# untitled.net
KiCad netlist of a schematic drawn in EAGLE
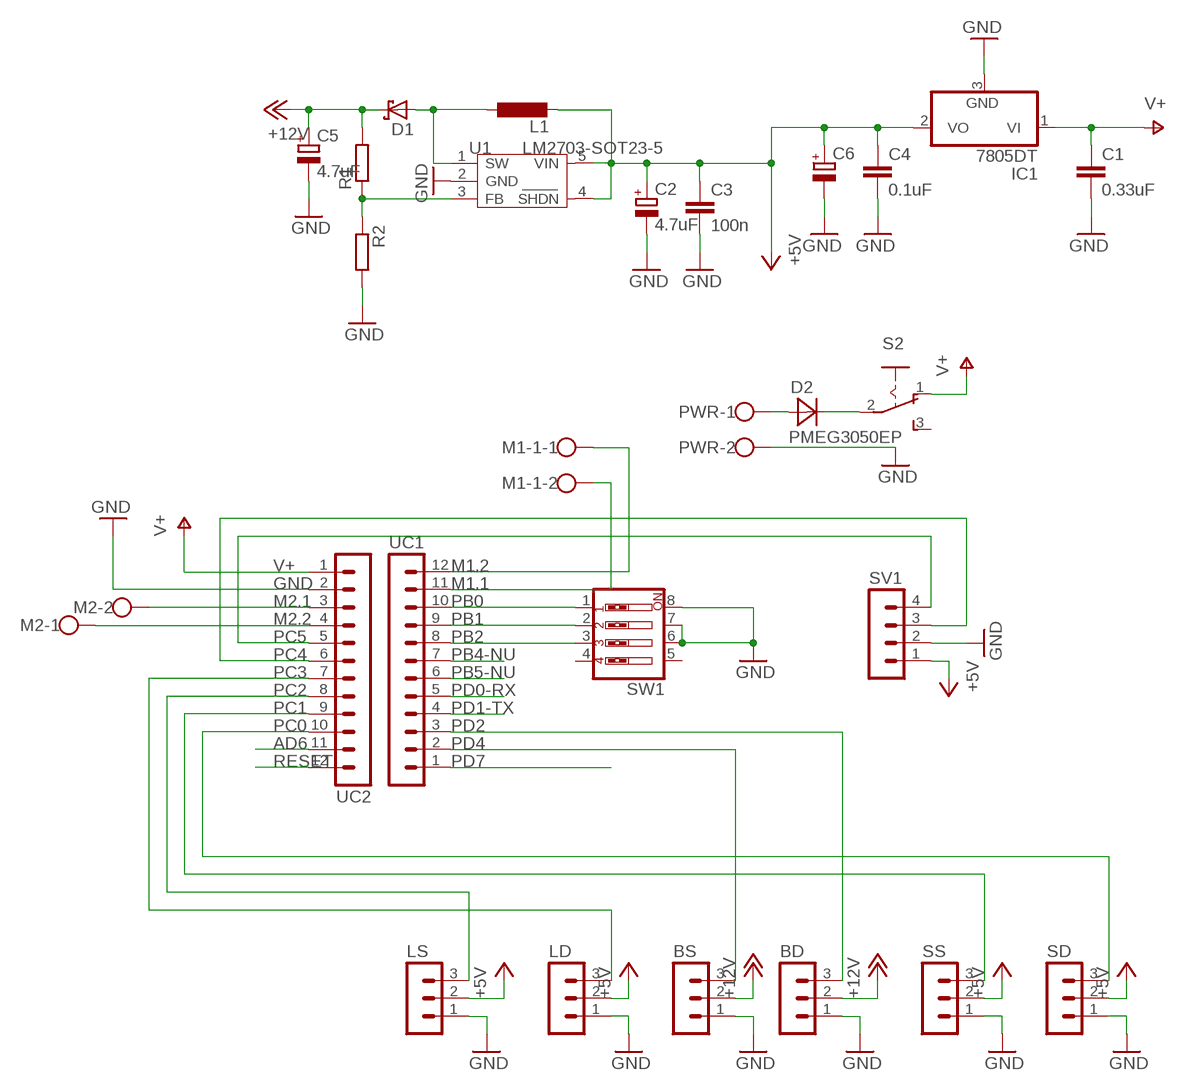
[diagram p0: schematic, sheet 1]

(export (version "E")
  (design (tool "Eeschema 10.0.6"))
  (components
    (comp (ref "BD")
      (value "MA03-1")
      (footprint "eagle-import:MA03-1")
      (libsource (lib "eagle-import") (part "MA03-1"))
    )
    (comp (ref "BS")
      (value "MA03-1")
      (footprint "eagle-import:MA03-1")
      (libsource (lib "eagle-import") (part "MA03-1"))
    )
    (comp (ref "C1")
      (value "0.33uF")
      (footprint "eagle-import:C0805")
      (libsource (lib "eagle-import") (part "C-EUC0805"))
    )
    (comp (ref "C2")
      (value "4.7uF")
      (footprint "eagle-import:153CLV-0405")
      (libsource (lib "eagle-import") (part "CPOL-EU153CLV-0405"))
    )
    (comp (ref "C3")
      (value "100n")
      (footprint "eagle-import:C0805")
      (libsource (lib "eagle-import") (part "C-EUC0805"))
    )
    (comp (ref "C4")
      (value "0.1uF")
      (footprint "eagle-import:C0805")
      (libsource (lib "eagle-import") (part "C-EUC0805"))
    )
    (comp (ref "C5")
      (value "4.7uF")
      (footprint "eagle-import:153CLV-0405")
      (libsource (lib "eagle-import") (part "CPOL-EU153CLV-0405"))
    )
    (comp (ref "C6")
      (value "CPOL-EU153CLV-0605")
      (footprint "eagle-import:153CLV-0605")
      (libsource (lib "eagle-import") (part "CPOL-EU153CLV-0605"))
    )
    (comp (ref "D1")
      (value "SCHOTTKY-DIODESMD")
      (footprint "eagle-import:SMB")
      (libsource (lib "eagle-import") (part "SCHOTTKY-DIODESMD"))
    )
    (comp (ref "D2")
      (value "PMEG3050EP")
      (footprint "eagle-import:SMA")
      (libsource (lib "eagle-import") (part "MBRA340T3"))
    )
    (comp (ref "IC1")
      (value "7805DT")
      (footprint "eagle-import:TO252")
      (libsource (lib "eagle-import") (part "78DT05"))
    )
    (comp (ref "L1")
      (value "L-EUL4532C")
      (footprint "eagle-import:L4532M")
      (libsource (lib "eagle-import") (part "L-EUL4532C"))
    )
    (comp (ref "LD")
      (value "MA03-1")
      (footprint "eagle-import:MA03-1")
      (libsource (lib "eagle-import") (part "MA03-1"))
    )
    (comp (ref "LS")
      (value "MA03-1")
      (footprint "eagle-import:MA03-1")
      (libsource (lib "eagle-import") (part "MA03-1"))
    )
    (comp (ref "M1-1")
      (value "W237-102")
      (footprint "eagle-import:W237-102")
      (fields (field (name "MPN") "237-102"))
      (libsource (lib "eagle-import") (part "W237-102"))
    )
    (comp (ref "M2")
      (value "W237-102")
      (footprint "eagle-import:W237-102")
      (fields (field (name "MPN") "237-102"))
      (libsource (lib "eagle-import") (part "W237-102"))
    )
    (comp (ref "PWR")
      (value "W237-102")
      (footprint "eagle-import:W237-102")
      (fields (field (name "MPN") "237-102"))
      (libsource (lib "eagle-import") (part "W237-102"))
    )
    (comp (ref "R1")
      (value "R-EU_R0805")
      (footprint "eagle-import:R0805")
      (libsource (lib "eagle-import") (part "R-EU_R0805"))
    )
    (comp (ref "R2")
      (value "R-EU_R0805")
      (footprint "eagle-import:R0805")
      (libsource (lib "eagle-import") (part "R-EU_R0805"))
    )
    (comp (ref "S2")
      (value "M251")
      (footprint "eagle-import:M251")
      (libsource (lib "eagle-import") (part "M251"))
    )
    (comp (ref "SD")
      (value "MA03-1")
      (footprint "eagle-import:MA03-1")
      (libsource (lib "eagle-import") (part "MA03-1"))
    )
    (comp (ref "SS")
      (value "MA03-1")
      (footprint "eagle-import:MA03-1")
      (libsource (lib "eagle-import") (part "MA03-1"))
    )
    (comp (ref "SV1")
      (value "MA04-1")
      (footprint "eagle-import:MA04-1")
      (libsource (lib "eagle-import") (part "MA04-1"))
    )
    (comp (ref "SW1")
      (value "SW_DIP-4")
      (footprint "eagle-import:EDG-04")
      (libsource (lib "eagle-import") (part "SW_DIP-4"))
    )
    (comp (ref "U1")
      (value "LM2703-SOT23-5")
      (footprint "eagle-import:SOT23-5")
      (libsource (lib "eagle-import") (part "LM2703-SOT23-5"))
    )
    (comp (ref "UC1")
      (value "MA12-1")
      (footprint "eagle-import:MA12-1")
      (fields (field (name "OC_FARNELL") "unknown") (field (name "OC_NEWARK") "unknown"))
      (libsource (lib "eagle-import") (part "MA12-1"))
    )
    (comp (ref "UC2")
      (value "MA12-1")
      (footprint "eagle-import:MA12-1")
      (libsource (lib "eagle-import") (part "MA12-1"))
    )
  )
  (nets
    (net (code "1") (name "+5V") (class "Default")
      (node (ref "C2") (pin "+") (pinfunction "+_+") (pintype "passive"))
      (node (ref "C3") (pin "1") (pinfunction "1_1") (pintype "passive"))
      (node (ref "C4") (pin "1") (pinfunction "1_1") (pintype "passive"))
      (node (ref "C6") (pin "+") (pinfunction "+_+") (pintype "passive"))
      (node (ref "IC1") (pin "2") (pinfunction "VO_2") (pintype "passive"))
      (node (ref "L1") (pin "2") (pinfunction "2_2") (pintype "passive"))
      (node (ref "LD") (pin "2") (pinfunction "2_2") (pintype "passive"))
      (node (ref "LS") (pin "2") (pinfunction "2_2") (pintype "passive"))
      (node (ref "SD") (pin "2") (pinfunction "2_2") (pintype "passive"))
      (node (ref "SS") (pin "2") (pinfunction "2_2") (pintype "passive"))
      (node (ref "SV1") (pin "1") (pinfunction "1_1") (pintype "passive"))
      (node (ref "U1") (pin "4") (pinfunction "SHDN_4") (pintype "bidirectional"))
      (node (ref "U1") (pin "5") (pinfunction "VIN_5") (pintype "input"))
    )
    (net (code "2") (name "+12V") (class "Default")
      (node (ref "BD") (pin "2") (pinfunction "2_2") (pintype "passive"))
      (node (ref "BS") (pin "2") (pinfunction "2_2") (pintype "passive"))
      (node (ref "C5") (pin "+") (pinfunction "+_+") (pintype "passive"))
      (node (ref "D1") (pin "C") (pinfunction "C_C") (pintype "passive"))
      (node (ref "R1") (pin "2") (pinfunction "2_2") (pintype "passive"))
    )
    (net (code "3") (name "/AD6") (class "Default")
      (node (ref "UC2") (pin "11") (pinfunction "11_11") (pintype "passive"))
    )
    (net (code "4") (name "/M1.1") (class "Default")
      (node (ref "M1-1") (pin "2") (pinfunction "KL_2") (pintype "passive"))
      (node (ref "UC1") (pin "11") (pinfunction "11_11") (pintype "passive"))
    )
    (net (code "5") (name "/M1.2") (class "Default")
      (node (ref "M1-1") (pin "1") (pinfunction "KL_1") (pintype "passive"))
      (node (ref "UC1") (pin "12") (pinfunction "12_12") (pintype "passive"))
    )
    (net (code "6") (name "/M2.1") (class "Default")
      (node (ref "M2") (pin "2") (pinfunction "KL_2") (pintype "passive"))
      (node (ref "UC2") (pin "3") (pinfunction "3_3") (pintype "passive"))
    )
    (net (code "7") (name "/M2.2") (class "Default")
      (node (ref "M2") (pin "1") (pinfunction "KL_1") (pintype "passive"))
      (node (ref "UC2") (pin "4") (pinfunction "4_4") (pintype "passive"))
    )
    (net (code "8") (name "/PB0") (class "Default")
      (node (ref "SW1") (pin "1") (pinfunction "1_1") (pintype "passive"))
      (node (ref "UC1") (pin "10") (pinfunction "10_10") (pintype "passive"))
    )
    (net (code "9") (name "/PB1") (class "Default")
      (node (ref "SW1") (pin "2") (pinfunction "2_2") (pintype "passive"))
      (node (ref "UC1") (pin "9") (pinfunction "9_9") (pintype "passive"))
    )
    (net (code "10") (name "/PB2") (class "Default")
      (node (ref "SW1") (pin "3") (pinfunction "3_3") (pintype "passive"))
      (node (ref "UC1") (pin "8") (pinfunction "8_8") (pintype "passive"))
    )
    (net (code "11") (name "/PB4-NU") (class "Default")
      (node (ref "UC1") (pin "7") (pinfunction "7_7") (pintype "passive"))
    )
    (net (code "12") (name "/PB5-NU") (class "Default")
      (node (ref "UC1") (pin "6") (pinfunction "6_6") (pintype "passive"))
    )
    (net (code "13") (name "/PC0") (class "Default")
      (node (ref "SD") (pin "3") (pinfunction "3_3") (pintype "passive"))
      (node (ref "UC2") (pin "10") (pinfunction "10_10") (pintype "passive"))
    )
    (net (code "14") (name "/PC1") (class "Default")
      (node (ref "SS") (pin "3") (pinfunction "3_3") (pintype "passive"))
      (node (ref "UC2") (pin "9") (pinfunction "9_9") (pintype "passive"))
    )
    (net (code "15") (name "/PC2") (class "Default")
      (node (ref "LS") (pin "3") (pinfunction "3_3") (pintype "passive"))
      (node (ref "UC2") (pin "8") (pinfunction "8_8") (pintype "passive"))
    )
    (net (code "16") (name "/PC3") (class "Default")
      (node (ref "LD") (pin "3") (pinfunction "3_3") (pintype "passive"))
      (node (ref "UC2") (pin "7") (pinfunction "7_7") (pintype "passive"))
    )
    (net (code "17") (name "/PC4") (class "Default")
      (node (ref "SV1") (pin "3") (pinfunction "3_3") (pintype "passive"))
      (node (ref "UC2") (pin "6") (pinfunction "6_6") (pintype "passive"))
    )
    (net (code "18") (name "/PC5") (class "Default")
      (node (ref "SV1") (pin "4") (pinfunction "4_4") (pintype "passive"))
      (node (ref "UC2") (pin "5") (pinfunction "5_5") (pintype "passive"))
    )
    (net (code "19") (name "/PD0-RX") (class "Default")
      (node (ref "UC1") (pin "5") (pinfunction "5_5") (pintype "passive"))
    )
    (net (code "20") (name "/PD1-TX") (class "Default")
      (node (ref "UC1") (pin "4") (pinfunction "4_4") (pintype "passive"))
    )
    (net (code "21") (name "/PD2") (class "Default")
      (node (ref "BD") (pin "3") (pinfunction "3_3") (pintype "passive"))
      (node (ref "UC1") (pin "3") (pinfunction "3_3") (pintype "passive"))
    )
    (net (code "22") (name "/PD4") (class "Default")
      (node (ref "BS") (pin "3") (pinfunction "3_3") (pintype "passive"))
      (node (ref "UC1") (pin "2") (pinfunction "2_2") (pintype "passive"))
    )
    (net (code "23") (name "/PD7") (class "Default")
      (node (ref "UC1") (pin "1") (pinfunction "1_1") (pintype "passive"))
    )
    (net (code "24") (name "/RESET") (class "Default")
      (node (ref "UC2") (pin "12") (pinfunction "12_12") (pintype "passive"))
    )
    (net (code "25") (name "GND") (class "Default")
      (node (ref "BD") (pin "1") (pinfunction "1_1") (pintype "passive"))
      (node (ref "BS") (pin "1") (pinfunction "1_1") (pintype "passive"))
      (node (ref "C1") (pin "2") (pinfunction "2_2") (pintype "passive"))
      (node (ref "C2") (pin "-") (pinfunction "-_-") (pintype "passive"))
      (node (ref "C3") (pin "2") (pinfunction "2_2") (pintype "passive"))
      (node (ref "C4") (pin "2") (pinfunction "2_2") (pintype "passive"))
      (node (ref "C5") (pin "-") (pinfunction "-_-") (pintype "passive"))
      (node (ref "C6") (pin "-") (pinfunction "-_-") (pintype "passive"))
      (node (ref "IC1") (pin "3") (pinfunction "GND_3") (pintype "passive"))
      (node (ref "LD") (pin "1") (pinfunction "1_1") (pintype "passive"))
      (node (ref "LS") (pin "1") (pinfunction "1_1") (pintype "passive"))
      (node (ref "PWR") (pin "2") (pinfunction "KL_2") (pintype "passive"))
      (node (ref "R2") (pin "2") (pinfunction "2_2") (pintype "passive"))
      (node (ref "SD") (pin "1") (pinfunction "1_1") (pintype "passive"))
      (node (ref "SS") (pin "1") (pinfunction "1_1") (pintype "passive"))
      (node (ref "SV1") (pin "2") (pinfunction "2_2") (pintype "passive"))
      (node (ref "SW1") (pin "6") (pinfunction "6_6") (pintype "passive"))
      (node (ref "SW1") (pin "7") (pinfunction "7_7") (pintype "passive"))
      (node (ref "SW1") (pin "8") (pinfunction "8_8") (pintype "passive"))
      (node (ref "U1") (pin "2") (pinfunction "GND_2") (pintype "power_in"))
      (node (ref "UC2") (pin "2") (pinfunction "2_2") (pintype "passive"))
    )
    (net (code "26") (name "Net-(PWRA-KL)") (class "Default")
      (node (ref "D2") (pin "A") (pinfunction "A_A") (pintype "passive"))
      (node (ref "PWR") (pin "1") (pinfunction "KL_1") (pintype "passive"))
    )
    (net (code "27") (name "Net-(S2-P)") (class "Default")
      (node (ref "D2") (pin "C") (pinfunction "C_C") (pintype "passive"))
      (node (ref "S2") (pin "2") (pinfunction "P_2") (pintype "passive"))
    )
    (net (code "28") (name "Net-(U1-FB)") (class "Default")
      (node (ref "R1") (pin "1") (pinfunction "1_1") (pintype "passive"))
      (node (ref "R2") (pin "1") (pinfunction "1_1") (pintype "passive"))
      (node (ref "U1") (pin "3") (pinfunction "FB_3") (pintype "input"))
    )
    (net (code "29") (name "Net-(U1-SW)") (class "Default")
      (node (ref "D1") (pin "A") (pinfunction "A_A") (pintype "passive"))
      (node (ref "L1") (pin "1") (pinfunction "1_1") (pintype "passive"))
      (node (ref "U1") (pin "1") (pinfunction "SW_1") (pintype "input"))
    )
    (net (code "30") (name "V+") (class "Default")
      (node (ref "C1") (pin "1") (pinfunction "1_1") (pintype "passive"))
      (node (ref "IC1") (pin "1") (pinfunction "VI_1") (pintype "input"))
      (node (ref "S2") (pin "1") (pinfunction "O_1") (pintype "passive"))
      (node (ref "UC2") (pin "1") (pinfunction "1_1") (pintype "passive"))
    )
    (net (code "31") (name "unconnected-(S2-S-Pad3)") (class "Default")
      (node (ref "S2") (pin "3") (pinfunction "S_3") (pintype "passive"))
    )
    (net (code "32") (name "unconnected-(SW1-Pad4)") (class "Default")
      (node (ref "SW1") (pin "4") (pinfunction "4_4") (pintype "passive"))
    )
    (net (code "33") (name "unconnected-(SW1-Pad5)") (class "Default")
      (node (ref "SW1") (pin "5") (pinfunction "5_5") (pintype "passive"))
    )
  )
)
